# failoverBoard.net
KiCad netlist of a schematic drawn in EAGLE
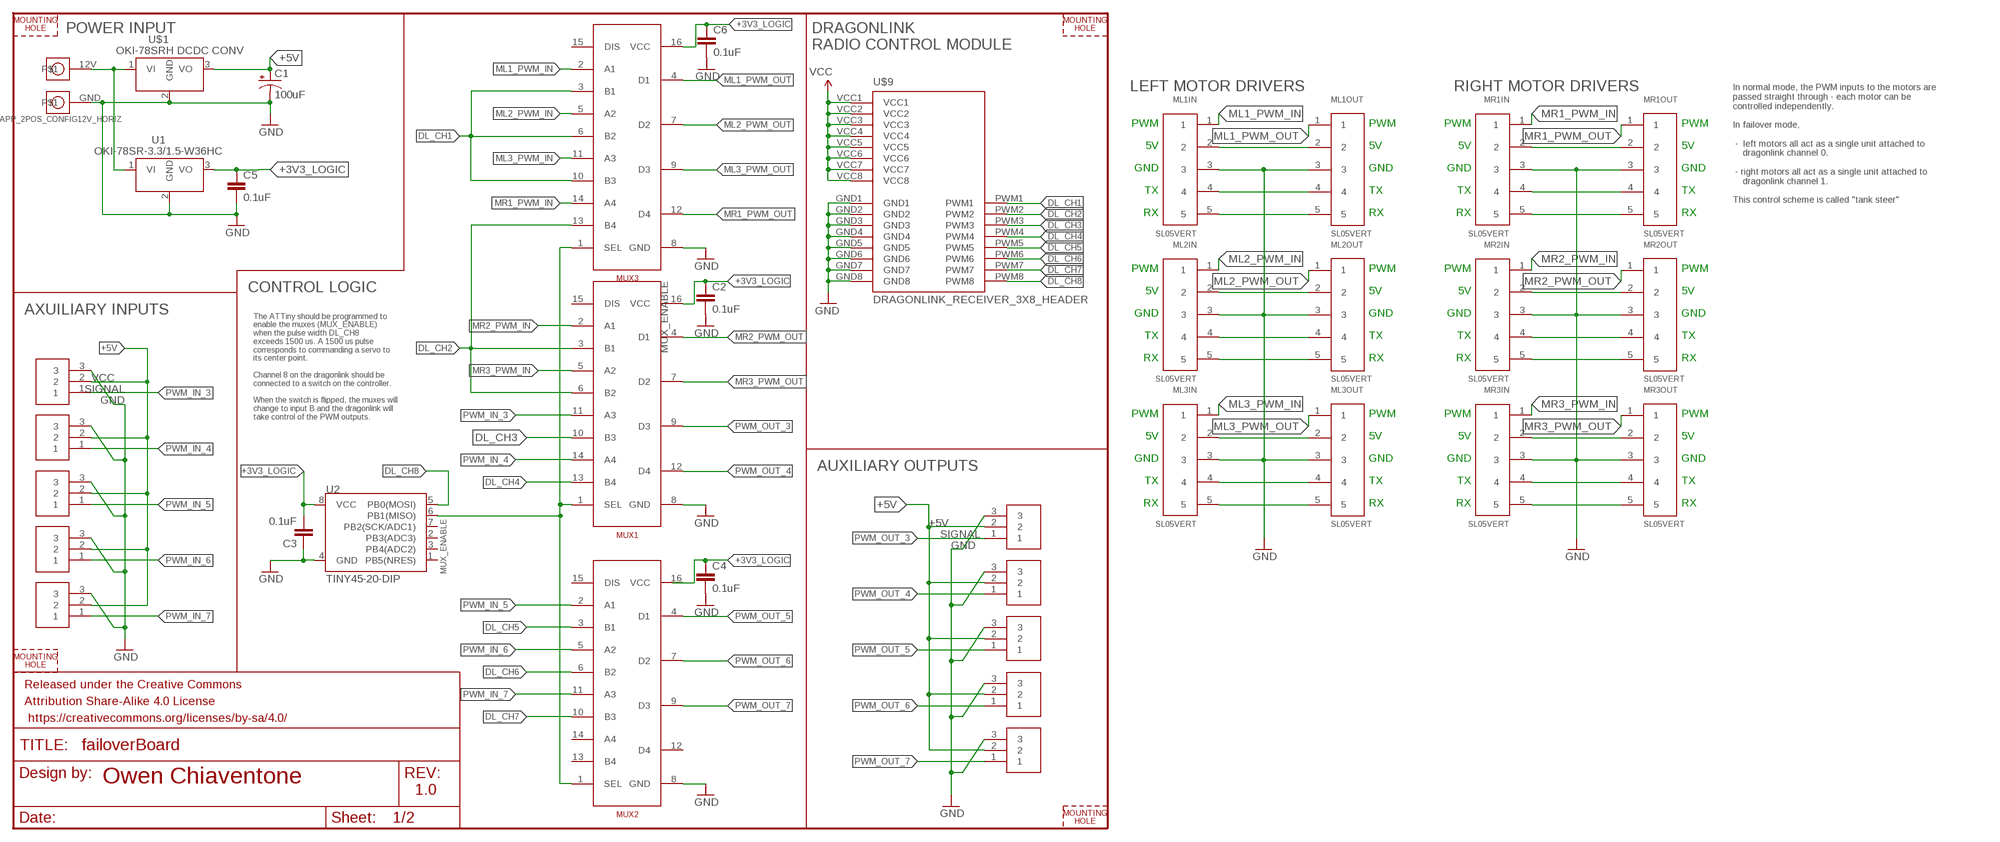
[diagram p0: schematic, sheet 1]

(export (version "E")
  (design (tool "Eeschema 10.0.6"))
  (components
    (comp (ref "C1")
      (value "100uF")
      (footprint "eagle-import:C_3.5MM")
      (libsource (lib "eagle-import") (part "C_UHE1H121MPD1TD"))
    )
    (comp (ref "C2")
      (value "0.1uF")
      (footprint "eagle-import:BOOST_CMP_0603-CAP")
      (libsource (lib "eagle-import") (part "BOOST_CMP_CAP0603-CAP"))
    )
    (comp (ref "C3")
      (value "0.1uF")
      (footprint "eagle-import:BOOST_CMP_0603-CAP")
      (libsource (lib "eagle-import") (part "BOOST_CMP_CAP0603-CAP"))
    )
    (comp (ref "C4")
      (value "0.1uF")
      (footprint "eagle-import:BOOST_CMP_0603-CAP")
      (libsource (lib "eagle-import") (part "BOOST_CMP_CAP0603-CAP"))
    )
    (comp (ref "C5")
      (value "0.1uF")
      (footprint "eagle-import:0603-CAP")
      (libsource (lib "eagle-import") (part "CAP0603-CAP"))
    )
    (comp (ref "C6")
      (value "0.1uF")
      (footprint "eagle-import:BOOST_CMP_0603-CAP")
      (libsource (lib "eagle-import") (part "BOOST_CMP_CAP0603-CAP"))
    )
    (comp (ref "FRAME1")
      (value "FRAME-LETTER")
      (footprint "eagle-import:CREATIVE_COMMONS")
      (libsource (lib "eagle-import") (part "FRAME-LETTER"))
    )
    (comp (ref "IN3")
      (value "SIERRAALTO.CONN.SUPPLEMENT_CONN_3MOLEX_0705550037")
      (footprint "eagle-import:SIERRAALTO.CONN.SUPPLEMENT_MOLEX_0705550037_3")
      (libsource (lib "eagle-import") (part "SIERRAALTO.CONN.SUPPLEMENT_CONN_3MOLEX_0705550037"))
    )
    (comp (ref "IN4")
      (value "SIERRAALTO.CONN.SUPPLEMENT_CONN_3MOLEX_0705550037")
      (footprint "eagle-import:SIERRAALTO.CONN.SUPPLEMENT_MOLEX_0705550037_3")
      (libsource (lib "eagle-import") (part "SIERRAALTO.CONN.SUPPLEMENT_CONN_3MOLEX_0705550037"))
    )
    (comp (ref "IN5")
      (value "SIERRAALTO.CONN.SUPPLEMENT_CONN_3MOLEX_0705550037")
      (footprint "eagle-import:SIERRAALTO.CONN.SUPPLEMENT_MOLEX_0705550037_3")
      (libsource (lib "eagle-import") (part "SIERRAALTO.CONN.SUPPLEMENT_CONN_3MOLEX_0705550037"))
    )
    (comp (ref "IN6")
      (value "SIERRAALTO.CONN.SUPPLEMENT_CONN_3MOLEX_0705550037")
      (footprint "eagle-import:SIERRAALTO.CONN.SUPPLEMENT_MOLEX_0705550037_3")
      (libsource (lib "eagle-import") (part "SIERRAALTO.CONN.SUPPLEMENT_CONN_3MOLEX_0705550037"))
    )
    (comp (ref "IN7")
      (value "SIERRAALTO.CONN.SUPPLEMENT_CONN_3MOLEX_0705550037")
      (footprint "eagle-import:SIERRAALTO.CONN.SUPPLEMENT_MOLEX_0705550037_3")
      (libsource (lib "eagle-import") (part "SIERRAALTO.CONN.SUPPLEMENT_CONN_3MOLEX_0705550037"))
    )
    (comp (ref "J1")
      (value "APP_2POS_CONFIG12V_HORIZ")
      (footprint "eagle-import:APP45_12V_HORIZ_CONFIG")
      (libsource (lib "eagle-import") (part "APP_2POS_CONFIG12V_HORIZ"))
    )
    (comp (ref "ML1IN")
      (value "SL05VERT")
      (footprint "eagle-import:MOLEX-70543-0004")
      (libsource (lib "eagle-import") (part "SL05VERT"))
    )
    (comp (ref "ML1OUT")
      (value "SL05VERT")
      (footprint "eagle-import:MOLEX-70543-0004")
      (libsource (lib "eagle-import") (part "SL05VERT"))
    )
    (comp (ref "ML2IN")
      (value "SL05VERT")
      (footprint "eagle-import:MOLEX-70543-0004")
      (libsource (lib "eagle-import") (part "SL05VERT"))
    )
    (comp (ref "ML2OUT")
      (value "SL05VERT")
      (footprint "eagle-import:MOLEX-70543-0004")
      (libsource (lib "eagle-import") (part "SL05VERT"))
    )
    (comp (ref "ML3IN")
      (value "SL05VERT")
      (footprint "eagle-import:MOLEX-70543-0004")
      (libsource (lib "eagle-import") (part "SL05VERT"))
    )
    (comp (ref "ML3OUT")
      (value "SL05VERT")
      (footprint "eagle-import:MOLEX-70543-0004")
      (libsource (lib "eagle-import") (part "SL05VERT"))
    )
    (comp (ref "MR1IN")
      (value "SL05VERT")
      (footprint "eagle-import:MOLEX-70543-0004")
      (libsource (lib "eagle-import") (part "SL05VERT"))
    )
    (comp (ref "MR1OUT")
      (value "SL05VERT")
      (footprint "eagle-import:MOLEX-70543-0004")
      (libsource (lib "eagle-import") (part "SL05VERT"))
    )
    (comp (ref "MR2IN")
      (value "SL05VERT")
      (footprint "eagle-import:MOLEX-70543-0004")
      (libsource (lib "eagle-import") (part "SL05VERT"))
    )
    (comp (ref "MR2OUT")
      (value "SL05VERT")
      (footprint "eagle-import:MOLEX-70543-0004")
      (libsource (lib "eagle-import") (part "SL05VERT"))
    )
    (comp (ref "MR3IN")
      (value "SL05VERT")
      (footprint "eagle-import:MOLEX-70543-0004")
      (libsource (lib "eagle-import") (part "SL05VERT"))
    )
    (comp (ref "MR3OUT")
      (value "SL05VERT")
      (footprint "eagle-import:MOLEX-70543-0004")
      (libsource (lib "eagle-import") (part "SL05VERT"))
    )
    (comp (ref "MUX1")
      (value "CD40257")
      (footprint "eagle-import:SOIC16")
      (libsource (lib "eagle-import") (part "CD40257"))
    )
    (comp (ref "MUX2")
      (value "CD40257")
      (footprint "eagle-import:SOIC16")
      (libsource (lib "eagle-import") (part "CD40257"))
    )
    (comp (ref "MUX3")
      (value "CD40257")
      (footprint "eagle-import:SOIC16")
      (libsource (lib "eagle-import") (part "CD40257"))
    )
    (comp (ref "OUT3")
      (value "SIERRAALTO.CONN.SUPPLEMENT_CONN_3MOLEX_0705550037")
      (footprint "eagle-import:SIERRAALTO.CONN.SUPPLEMENT_MOLEX_0705550037_3")
      (libsource (lib "eagle-import") (part "SIERRAALTO.CONN.SUPPLEMENT_CONN_3MOLEX_0705550037"))
    )
    (comp (ref "OUT4")
      (value "SIERRAALTO.CONN.SUPPLEMENT_CONN_3MOLEX_0705550037")
      (footprint "eagle-import:SIERRAALTO.CONN.SUPPLEMENT_MOLEX_0705550037_3")
      (libsource (lib "eagle-import") (part "SIERRAALTO.CONN.SUPPLEMENT_CONN_3MOLEX_0705550037"))
    )
    (comp (ref "OUT5")
      (value "SIERRAALTO.CONN.SUPPLEMENT_CONN_3MOLEX_0705550037")
      (footprint "eagle-import:SIERRAALTO.CONN.SUPPLEMENT_MOLEX_0705550037_3")
      (libsource (lib "eagle-import") (part "SIERRAALTO.CONN.SUPPLEMENT_CONN_3MOLEX_0705550037"))
    )
    (comp (ref "OUT6")
      (value "SIERRAALTO.CONN.SUPPLEMENT_CONN_3MOLEX_0705550037")
      (footprint "eagle-import:SIERRAALTO.CONN.SUPPLEMENT_MOLEX_0705550037_3")
      (libsource (lib "eagle-import") (part "SIERRAALTO.CONN.SUPPLEMENT_CONN_3MOLEX_0705550037"))
    )
    (comp (ref "OUT7")
      (value "SIERRAALTO.CONN.SUPPLEMENT_CONN_3MOLEX_0705550037")
      (footprint "eagle-import:SIERRAALTO.CONN.SUPPLEMENT_MOLEX_0705550037_3")
      (libsource (lib "eagle-import") (part "SIERRAALTO.CONN.SUPPLEMENT_CONN_3MOLEX_0705550037"))
    )
    (comp (ref "U$1")
      (value "Q_OKI-78SR")
      (footprint "eagle-import:OKI-78SR_HORIZ")
      (libsource (lib "eagle-import") (part "Q_OKI-78SR"))
    )
    (comp (ref "U$3")
      (value "MOUNTING_HOLE#6")
      (footprint "eagle-import:#6_SCREW")
      (libsource (lib "eagle-import") (part "MOUNTING_HOLE#6"))
    )
    (comp (ref "U$4")
      (value "MOUNTING_HOLE#6")
      (footprint "eagle-import:#6_SCREW")
      (libsource (lib "eagle-import") (part "MOUNTING_HOLE#6"))
    )
    (comp (ref "U$5")
      (value "MOUNTING_HOLE#6")
      (footprint "eagle-import:#6_SCREW")
      (libsource (lib "eagle-import") (part "MOUNTING_HOLE#6"))
    )
    (comp (ref "U$6")
      (value "MOUNTING_HOLE#6")
      (footprint "eagle-import:#6_SCREW")
      (libsource (lib "eagle-import") (part "MOUNTING_HOLE#6"))
    )
    (comp (ref "U$9")
      (value "DRAGONLINK_RECEIVER_3X8_HEADER")
      (footprint "eagle-import:3X8_HEADER_2.54MM")
      (libsource (lib "eagle-import") (part "DRAGONLINK_RECEIVER_3X8_HEADER"))
    )
    (comp (ref "U1")
      (value "OKI-78SR-3.3/1.5-W36HC")
      (footprint "eagle-import:OKI-78SR_HORIZ")
      (libsource (lib "eagle-import") (part "OKI-78SR-/1.5-W36?CH3.3"))
    )
    (comp (ref "U2")
      (value "TINY45-20-DIP")
      (footprint "eagle-import:DIP08")
      (libsource (lib "eagle-import") (part "ATTINY45TINY45-20-DIP"))
    )
  )
  (nets
    (net (code "1") (name "+3V3_LOGIC") (class "Default")
      (node (ref "C2") (pin "1") (pinfunction "1_1") (pintype "passive"))
      (node (ref "C3") (pin "2") (pinfunction "2_2") (pintype "passive"))
      (node (ref "C4") (pin "1") (pinfunction "1_1") (pintype "passive"))
      (node (ref "C5") (pin "1") (pinfunction "1_1") (pintype "passive"))
      (node (ref "C6") (pin "1") (pinfunction "1_1") (pintype "passive"))
      (node (ref "MUX1") (pin "16") (pinfunction "VCC_16") (pintype "bidirectional"))
      (node (ref "MUX2") (pin "16") (pinfunction "VCC_16") (pintype "bidirectional"))
      (node (ref "MUX3") (pin "16") (pinfunction "VCC_16") (pintype "bidirectional"))
      (node (ref "U1") (pin "3") (pinfunction "VO_3") (pintype "bidirectional"))
      (node (ref "U2") (pin "8") (pinfunction "VCC_8") (pintype "bidirectional"))
    )
    (net (code "2") (name "+5V") (class "Default")
      (node (ref "C1") (pin "+") (pinfunction "+_+") (pintype "passive"))
      (node (ref "IN3") (pin "2") (pinfunction "2_2") (pintype "bidirectional"))
      (node (ref "IN4") (pin "2") (pinfunction "2_2") (pintype "bidirectional"))
      (node (ref "IN5") (pin "2") (pinfunction "2_2") (pintype "bidirectional"))
      (node (ref "IN6") (pin "2") (pinfunction "2_2") (pintype "bidirectional"))
      (node (ref "IN7") (pin "2") (pinfunction "2_2") (pintype "bidirectional"))
      (node (ref "OUT3") (pin "2") (pinfunction "2_2") (pintype "bidirectional"))
      (node (ref "OUT4") (pin "2") (pinfunction "2_2") (pintype "bidirectional"))
      (node (ref "OUT5") (pin "2") (pinfunction "2_2") (pintype "bidirectional"))
      (node (ref "OUT6") (pin "2") (pinfunction "2_2") (pintype "bidirectional"))
      (node (ref "OUT7") (pin "2") (pinfunction "2_2") (pintype "bidirectional"))
      (node (ref "U$1") (pin "3") (pinfunction "VO_3") (pintype "bidirectional"))
    )
    (net (code "3") (name "DL_CH1") (class "Default")
      (node (ref "MUX3") (pin "10") (pinfunction "B3_10") (pintype "bidirectional"))
      (node (ref "MUX3") (pin "3") (pinfunction "B1_3") (pintype "bidirectional"))
      (node (ref "MUX3") (pin "6") (pinfunction "B2_6") (pintype "bidirectional"))
      (node (ref "U$9") (pin "PWM1") (pinfunction "PWM1_PWM1") (pintype "output"))
    )
    (net (code "4") (name "DL_CH2") (class "Default")
      (node (ref "MUX1") (pin "3") (pinfunction "B1_3") (pintype "bidirectional"))
      (node (ref "MUX1") (pin "6") (pinfunction "B2_6") (pintype "bidirectional"))
      (node (ref "MUX3") (pin "13") (pinfunction "B4_13") (pintype "bidirectional"))
      (node (ref "U$9") (pin "PWM2") (pinfunction "PWM2_PWM2") (pintype "output"))
    )
    (net (code "5") (name "DL_CH3") (class "Default")
      (node (ref "MUX1") (pin "10") (pinfunction "B3_10") (pintype "bidirectional"))
      (node (ref "U$9") (pin "PWM3") (pinfunction "PWM3_PWM3") (pintype "output"))
    )
    (net (code "6") (name "DL_CH4") (class "Default")
      (node (ref "MUX1") (pin "13") (pinfunction "B4_13") (pintype "bidirectional"))
      (node (ref "U$9") (pin "PWM4") (pinfunction "PWM4_PWM4") (pintype "output"))
    )
    (net (code "7") (name "DL_CH5") (class "Default")
      (node (ref "MUX2") (pin "3") (pinfunction "B1_3") (pintype "bidirectional"))
      (node (ref "U$9") (pin "PWM5") (pinfunction "PWM5_PWM5") (pintype "output"))
    )
    (net (code "8") (name "DL_CH6") (class "Default")
      (node (ref "MUX2") (pin "6") (pinfunction "B2_6") (pintype "bidirectional"))
      (node (ref "U$9") (pin "PWM6") (pinfunction "PWM6_PWM6") (pintype "output"))
    )
    (net (code "9") (name "DL_CH7") (class "Default")
      (node (ref "MUX2") (pin "10") (pinfunction "B3_10") (pintype "bidirectional"))
      (node (ref "U$9") (pin "PWM7") (pinfunction "PWM7_PWM7") (pintype "output"))
    )
    (net (code "10") (name "DL_CH8") (class "Default")
      (node (ref "U$9") (pin "PWM8") (pinfunction "PWM8_PWM8") (pintype "output"))
      (node (ref "U2") (pin "5") (pinfunction "PB0(MOSI)_5") (pintype "bidirectional"))
    )
    (net (code "11") (name "GND") (class "Default")
      (node (ref "C1") (pin "-") (pinfunction "-_-") (pintype "passive"))
      (node (ref "C2") (pin "2") (pinfunction "2_2") (pintype "passive"))
      (node (ref "C3") (pin "1") (pinfunction "1_1") (pintype "passive"))
      (node (ref "C4") (pin "2") (pinfunction "2_2") (pintype "passive"))
      (node (ref "C5") (pin "2") (pinfunction "2_2") (pintype "passive"))
      (node (ref "C6") (pin "2") (pinfunction "2_2") (pintype "passive"))
      (node (ref "IN3") (pin "3") (pinfunction "3_3") (pintype "bidirectional"))
      (node (ref "IN4") (pin "3") (pinfunction "3_3") (pintype "bidirectional"))
      (node (ref "IN5") (pin "3") (pinfunction "3_3") (pintype "bidirectional"))
      (node (ref "IN6") (pin "3") (pinfunction "3_3") (pintype "bidirectional"))
      (node (ref "IN7") (pin "3") (pinfunction "3_3") (pintype "bidirectional"))
      (node (ref "J1") (pin "GND") (pinfunction "P$1_GND") (pintype "bidirectional"))
      (node (ref "ML1IN") (pin "3") (pinfunction "3_3") (pintype "bidirectional"))
      (node (ref "ML1OUT") (pin "3") (pinfunction "3_3") (pintype "bidirectional"))
      (node (ref "ML2IN") (pin "3") (pinfunction "3_3") (pintype "bidirectional"))
      (node (ref "ML2OUT") (pin "3") (pinfunction "3_3") (pintype "bidirectional"))
      (node (ref "ML3IN") (pin "3") (pinfunction "3_3") (pintype "bidirectional"))
      (node (ref "ML3OUT") (pin "3") (pinfunction "3_3") (pintype "bidirectional"))
      (node (ref "MR1IN") (pin "3") (pinfunction "3_3") (pintype "bidirectional"))
      (node (ref "MR1OUT") (pin "3") (pinfunction "3_3") (pintype "bidirectional"))
      (node (ref "MR2IN") (pin "3") (pinfunction "3_3") (pintype "bidirectional"))
      (node (ref "MR2OUT") (pin "3") (pinfunction "3_3") (pintype "bidirectional"))
      (node (ref "MR3IN") (pin "3") (pinfunction "3_3") (pintype "bidirectional"))
      (node (ref "MR3OUT") (pin "3") (pinfunction "3_3") (pintype "bidirectional"))
      (node (ref "MUX1") (pin "8") (pinfunction "GND_8") (pintype "bidirectional"))
      (node (ref "MUX2") (pin "8") (pinfunction "GND_8") (pintype "bidirectional"))
      (node (ref "MUX3") (pin "8") (pinfunction "GND_8") (pintype "bidirectional"))
      (node (ref "OUT3") (pin "3") (pinfunction "3_3") (pintype "bidirectional"))
      (node (ref "OUT4") (pin "3") (pinfunction "3_3") (pintype "bidirectional"))
      (node (ref "OUT5") (pin "3") (pinfunction "3_3") (pintype "bidirectional"))
      (node (ref "OUT6") (pin "3") (pinfunction "3_3") (pintype "bidirectional"))
      (node (ref "OUT7") (pin "3") (pinfunction "3_3") (pintype "bidirectional"))
      (node (ref "U$1") (pin "2") (pinfunction "GND_2") (pintype "bidirectional"))
      (node (ref "U$9") (pin "GND1") (pinfunction "GND1_GND1") (pintype "power_in"))
      (node (ref "U$9") (pin "GND2") (pinfunction "GND2_GND2") (pintype "power_in"))
      (node (ref "U$9") (pin "GND3") (pinfunction "GND3_GND3") (pintype "power_in"))
      (node (ref "U$9") (pin "GND4") (pinfunction "GND4_GND4") (pintype "power_in"))
      (node (ref "U$9") (pin "GND5") (pinfunction "GND5_GND5") (pintype "power_in"))
      (node (ref "U$9") (pin "GND6") (pinfunction "GND6_GND6") (pintype "power_in"))
      (node (ref "U$9") (pin "GND7") (pinfunction "GND7_GND7") (pintype "power_in"))
      (node (ref "U$9") (pin "GND8") (pinfunction "GND8_GND8") (pintype "power_in"))
      (node (ref "U1") (pin "2") (pinfunction "GND_2") (pintype "bidirectional"))
      (node (ref "U2") (pin "4") (pinfunction "GND_4") (pintype "bidirectional"))
    )
    (net (code "12") (name "ML1_PWM_IN") (class "Default")
      (node (ref "ML1IN") (pin "1") (pinfunction "1_1") (pintype "bidirectional"))
      (node (ref "MUX3") (pin "2") (pinfunction "A1_2") (pintype "bidirectional"))
    )
    (net (code "13") (name "ML1_PWM_OUT") (class "Default")
      (node (ref "ML1OUT") (pin "1") (pinfunction "1_1") (pintype "bidirectional"))
      (node (ref "MUX3") (pin "4") (pinfunction "D1_4") (pintype "bidirectional"))
    )
    (net (code "14") (name "ML2_PWM_IN") (class "Default")
      (node (ref "ML2IN") (pin "1") (pinfunction "1_1") (pintype "bidirectional"))
      (node (ref "MUX3") (pin "5") (pinfunction "A2_5") (pintype "bidirectional"))
    )
    (net (code "15") (name "ML2_PWM_OUT") (class "Default")
      (node (ref "ML2OUT") (pin "1") (pinfunction "1_1") (pintype "bidirectional"))
      (node (ref "MUX3") (pin "7") (pinfunction "D2_7") (pintype "bidirectional"))
    )
    (net (code "16") (name "ML3_PWM_IN") (class "Default")
      (node (ref "ML3IN") (pin "1") (pinfunction "1_1") (pintype "bidirectional"))
      (node (ref "MUX3") (pin "11") (pinfunction "A3_11") (pintype "bidirectional"))
    )
    (net (code "17") (name "ML3_PWM_OUT") (class "Default")
      (node (ref "ML3OUT") (pin "1") (pinfunction "1_1") (pintype "bidirectional"))
      (node (ref "MUX3") (pin "9") (pinfunction "D3_9") (pintype "bidirectional"))
    )
    (net (code "18") (name "MR1_PWM_IN") (class "Default")
      (node (ref "MR1IN") (pin "1") (pinfunction "1_1") (pintype "bidirectional"))
      (node (ref "MUX3") (pin "14") (pinfunction "A4_14") (pintype "bidirectional"))
    )
    (net (code "19") (name "MR1_PWM_OUT") (class "Default")
      (node (ref "MR1OUT") (pin "1") (pinfunction "1_1") (pintype "bidirectional"))
      (node (ref "MUX3") (pin "12") (pinfunction "D4_12") (pintype "bidirectional"))
    )
    (net (code "20") (name "MR2_PWM_IN") (class "Default")
      (node (ref "MR2IN") (pin "1") (pinfunction "1_1") (pintype "bidirectional"))
      (node (ref "MUX1") (pin "2") (pinfunction "A1_2") (pintype "bidirectional"))
    )
    (net (code "21") (name "MR2_PWM_OUT") (class "Default")
      (node (ref "MR2OUT") (pin "1") (pinfunction "1_1") (pintype "bidirectional"))
      (node (ref "MUX1") (pin "4") (pinfunction "D1_4") (pintype "bidirectional"))
    )
    (net (code "22") (name "MR3_PWM_IN") (class "Default")
      (node (ref "MR3IN") (pin "1") (pinfunction "1_1") (pintype "bidirectional"))
      (node (ref "MUX1") (pin "5") (pinfunction "A2_5") (pintype "bidirectional"))
    )
    (net (code "23") (name "MR3_PWM_OUT") (class "Default")
      (node (ref "MR3OUT") (pin "1") (pinfunction "1_1") (pintype "bidirectional"))
      (node (ref "MUX1") (pin "7") (pinfunction "D2_7") (pintype "bidirectional"))
    )
    (net (code "24") (name "MUX_ENABLE") (class "Default")
      (node (ref "MUX1") (pin "1") (pinfunction "SEL_1") (pintype "bidirectional"))
      (node (ref "MUX2") (pin "1") (pinfunction "SEL_1") (pintype "bidirectional"))
      (node (ref "MUX3") (pin "1") (pinfunction "SEL_1") (pintype "bidirectional"))
      (node (ref "U2") (pin "6") (pinfunction "PB1(MISO)_6") (pintype "bidirectional"))
    )
    (net (code "25") (name "Net-(J1B-P$1)") (class "Default")
      (node (ref "J1") (pin "12V") (pinfunction "P$1_12V") (pintype "bidirectional"))
      (node (ref "U$1") (pin "1") (pinfunction "VI_1") (pintype "bidirectional"))
      (node (ref "U1") (pin "1") (pinfunction "VI_1") (pintype "bidirectional"))
    )
    (net (code "26") (name "Net-(ML1IN-Pad2)") (class "Default")
      (node (ref "ML1IN") (pin "2") (pinfunction "2_2") (pintype "bidirectional"))
      (node (ref "ML1OUT") (pin "2") (pinfunction "2_2") (pintype "bidirectional"))
    )
    (net (code "27") (name "Net-(ML1IN-Pad4)") (class "Default")
      (node (ref "ML1IN") (pin "4") (pinfunction "4_4") (pintype "bidirectional"))
      (node (ref "ML1OUT") (pin "4") (pinfunction "4_4") (pintype "bidirectional"))
    )
    (net (code "28") (name "Net-(ML1IN-Pad5)") (class "Default")
      (node (ref "ML1IN") (pin "5") (pinfunction "5_5") (pintype "bidirectional"))
      (node (ref "ML1OUT") (pin "5") (pinfunction "5_5") (pintype "bidirectional"))
    )
    (net (code "29") (name "Net-(ML2IN-Pad2)") (class "Default")
      (node (ref "ML2IN") (pin "2") (pinfunction "2_2") (pintype "bidirectional"))
      (node (ref "ML2OUT") (pin "2") (pinfunction "2_2") (pintype "bidirectional"))
    )
    (net (code "30") (name "Net-(ML2IN-Pad4)") (class "Default")
      (node (ref "ML2IN") (pin "4") (pinfunction "4_4") (pintype "bidirectional"))
      (node (ref "ML2OUT") (pin "4") (pinfunction "4_4") (pintype "bidirectional"))
    )
    (net (code "31") (name "Net-(ML2IN-Pad5)") (class "Default")
      (node (ref "ML2IN") (pin "5") (pinfunction "5_5") (pintype "bidirectional"))
      (node (ref "ML2OUT") (pin "5") (pinfunction "5_5") (pintype "bidirectional"))
    )
    (net (code "32") (name "Net-(ML3IN-Pad2)") (class "Default")
      (node (ref "ML3IN") (pin "2") (pinfunction "2_2") (pintype "bidirectional"))
      (node (ref "ML3OUT") (pin "2") (pinfunction "2_2") (pintype "bidirectional"))
    )
    (net (code "33") (name "Net-(ML3IN-Pad4)") (class "Default")
      (node (ref "ML3IN") (pin "4") (pinfunction "4_4") (pintype "bidirectional"))
      (node (ref "ML3OUT") (pin "4") (pinfunction "4_4") (pintype "bidirectional"))
    )
    (net (code "34") (name "Net-(ML3IN-Pad5)") (class "Default")
      (node (ref "ML3IN") (pin "5") (pinfunction "5_5") (pintype "bidirectional"))
      (node (ref "ML3OUT") (pin "5") (pinfunction "5_5") (pintype "bidirectional"))
    )
    (net (code "35") (name "Net-(MR1IN-Pad2)") (class "Default")
      (node (ref "MR1IN") (pin "2") (pinfunction "2_2") (pintype "bidirectional"))
      (node (ref "MR1OUT") (pin "2") (pinfunction "2_2") (pintype "bidirectional"))
    )
    (net (code "36") (name "Net-(MR1IN-Pad4)") (class "Default")
      (node (ref "MR1IN") (pin "4") (pinfunction "4_4") (pintype "bidirectional"))
      (node (ref "MR1OUT") (pin "4") (pinfunction "4_4") (pintype "bidirectional"))
    )
    (net (code "37") (name "Net-(MR1IN-Pad5)") (class "Default")
      (node (ref "MR1IN") (pin "5") (pinfunction "5_5") (pintype "bidirectional"))
      (node (ref "MR1OUT") (pin "5") (pinfunction "5_5") (pintype "bidirectional"))
    )
    (net (code "38") (name "Net-(MR2IN-Pad2)") (class "Default")
      (node (ref "MR2IN") (pin "2") (pinfunction "2_2") (pintype "bidirectional"))
      (node (ref "MR2OUT") (pin "2") (pinfunction "2_2") (pintype "bidirectional"))
    )
    (net (code "39") (name "Net-(MR2IN-Pad4)") (class "Default")
      (node (ref "MR2IN") (pin "4") (pinfunction "4_4") (pintype "bidirectional"))
      (node (ref "MR2OUT") (pin "4") (pinfunction "4_4") (pintype "bidirectional"))
    )
    (net (code "40") (name "Net-(MR2IN-Pad5)") (class "Default")
      (node (ref "MR2IN") (pin "5") (pinfunction "5_5") (pintype "bidirectional"))
      (node (ref "MR2OUT") (pin "5") (pinfunction "5_5") (pintype "bidirectional"))
    )
    (net (code "41") (name "Net-(MR3IN-Pad2)") (class "Default")
      (node (ref "MR3IN") (pin "2") (pinfunction "2_2") (pintype "bidirectional"))
      (node (ref "MR3OUT") (pin "2") (pinfunction "2_2") (pintype "bidirectional"))
    )
    (net (code "42") (name "Net-(MR3IN-Pad4)") (class "Default")
      (node (ref "MR3IN") (pin "4") (pinfunction "4_4") (pintype "bidirectional"))
      (node (ref "MR3OUT") (pin "4") (pinfunction "4_4") (pintype "bidirectional"))
    )
    (net (code "43") (name "Net-(MR3IN-Pad5)") (class "Default")
      (node (ref "MR3IN") (pin "5") (pinfunction "5_5") (pintype "bidirectional"))
      (node (ref "MR3OUT") (pin "5") (pinfunction "5_5") (pintype "bidirectional"))
    )
    (net (code "44") (name "PWM_IN_3") (class "Default")
      (node (ref "IN3") (pin "1") (pinfunction "1_1") (pintype "bidirectional"))
      (node (ref "MUX1") (pin "11") (pinfunction "A3_11") (pintype "bidirectional"))
    )
    (net (code "45") (name "PWM_IN_4") (class "Default")
      (node (ref "IN4") (pin "1") (pinfunction "1_1") (pintype "bidirectional"))
      (node (ref "MUX1") (pin "14") (pinfunction "A4_14") (pintype "bidirectional"))
    )
    (net (code "46") (name "PWM_IN_5") (class "Default")
      (node (ref "IN5") (pin "1") (pinfunction "1_1") (pintype "bidirectional"))
      (node (ref "MUX2") (pin "2") (pinfunction "A1_2") (pintype "bidirectional"))
    )
    (net (code "47") (name "PWM_IN_6") (class "Default")
      (node (ref "IN6") (pin "1") (pinfunction "1_1") (pintype "bidirectional"))
      (node (ref "MUX2") (pin "5") (pinfunction "A2_5") (pintype "bidirectional"))
    )
    (net (code "48") (name "PWM_IN_7") (class "Default")
      (node (ref "IN7") (pin "1") (pinfunction "1_1") (pintype "bidirectional"))
      (node (ref "MUX2") (pin "11") (pinfunction "A3_11") (pintype "bidirectional"))
    )
    (net (code "49") (name "PWM_OUT_3") (class "Default")
      (node (ref "MUX1") (pin "9") (pinfunction "D3_9") (pintype "bidirectional"))
      (node (ref "OUT3") (pin "1") (pinfunction "1_1") (pintype "bidirectional"))
    )
    (net (code "50") (name "PWM_OUT_4") (class "Default")
      (node (ref "MUX1") (pin "12") (pinfunction "D4_12") (pintype "bidirectional"))
      (node (ref "OUT4") (pin "1") (pinfunction "1_1") (pintype "bidirectional"))
    )
    (net (code "51") (name "PWM_OUT_5") (class "Default")
      (node (ref "MUX2") (pin "4") (pinfunction "D1_4") (pintype "bidirectional"))
      (node (ref "OUT5") (pin "1") (pinfunction "1_1") (pintype "bidirectional"))
    )
    (net (code "52") (name "PWM_OUT_6") (class "Default")
      (node (ref "MUX2") (pin "7") (pinfunction "D2_7") (pintype "bidirectional"))
      (node (ref "OUT6") (pin "1") (pinfunction "1_1") (pintype "bidirectional"))
    )
    (net (code "53") (name "PWM_OUT_7") (class "Default")
      (node (ref "MUX2") (pin "9") (pinfunction "D3_9") (pintype "bidirectional"))
      (node (ref "OUT7") (pin "1") (pinfunction "1_1") (pintype "bidirectional"))
    )
    (net (code "54") (name "VCC") (class "Default")
      (node (ref "U$9") (pin "VCC1") (pinfunction "VCC1_VCC1") (pintype "power_in"))
      (node (ref "U$9") (pin "VCC2") (pinfunction "VCC2_VCC2") (pintype "power_in"))
      (node (ref "U$9") (pin "VCC3") (pinfunction "VCC3_VCC3") (pintype "power_in"))
      (node (ref "U$9") (pin "VCC4") (pinfunction "VCC4_VCC4") (pintype "power_in"))
      (node (ref "U$9") (pin "VCC5") (pinfunction "VCC5_VCC5") (pintype "power_in"))
      (node (ref "U$9") (pin "VCC6") (pinfunction "VCC6_VCC6") (pintype "power_in"))
      (node (ref "U$9") (pin "VCC7") (pinfunction "VCC7_VCC7") (pintype "power_in"))
      (node (ref "U$9") (pin "VCC8") (pinfunction "VCC8_VCC8") (pintype "power_in"))
    )
    (net (code "55") (name "unconnected-(MUX1-DIS-Pad15)") (class "Default")
      (node (ref "MUX1") (pin "15") (pinfunction "DIS_15") (pintype "bidirectional"))
    )
    (net (code "56") (name "unconnected-(MUX2-A4-Pad14)") (class "Default")
      (node (ref "MUX2") (pin "14") (pinfunction "A4_14") (pintype "bidirectional"))
    )
    (net (code "57") (name "unconnected-(MUX2-B4-Pad13)") (class "Default")
      (node (ref "MUX2") (pin "13") (pinfunction "B4_13") (pintype "bidirectional"))
    )
    (net (code "58") (name "unconnected-(MUX2-D4-Pad12)") (class "Default")
      (node (ref "MUX2") (pin "12") (pinfunction "D4_12") (pintype "bidirectional"))
    )
    (net (code "59") (name "unconnected-(MUX2-DIS-Pad15)") (class "Default")
      (node (ref "MUX2") (pin "15") (pinfunction "DIS_15") (pintype "bidirectional"))
    )
    (net (code "60") (name "unconnected-(MUX3-DIS-Pad15)") (class "Default")
      (node (ref "MUX3") (pin "15") (pinfunction "DIS_15") (pintype "bidirectional"))
    )
    (net (code "61") (name "unconnected-(U2-PB2(SCK{slash}ADC1)-Pad7)") (class "Default")
      (node (ref "U2") (pin "7") (pinfunction "PB2(SCK/ADC1)_7") (pintype "bidirectional"))
    )
    (net (code "62") (name "unconnected-(U2-PB3(ADC3)-Pad2)") (class "Default")
      (node (ref "U2") (pin "2") (pinfunction "PB3(ADC3)_2") (pintype "bidirectional"))
    )
    (net (code "63") (name "unconnected-(U2-PB4(ADC2)-Pad3)") (class "Default")
      (node (ref "U2") (pin "3") (pinfunction "PB4(ADC2)_3") (pintype "bidirectional"))
    )
    (net (code "64") (name "unconnected-(U2-PB5(NRES)-Pad1)") (class "Default")
      (node (ref "U2") (pin "1") (pinfunction "PB5(NRES)_1") (pintype "bidirectional"))
    )
  )
)
